# PiezoPreamp_V4-1.net
KiCad netlist of a schematic drawn in EAGLE
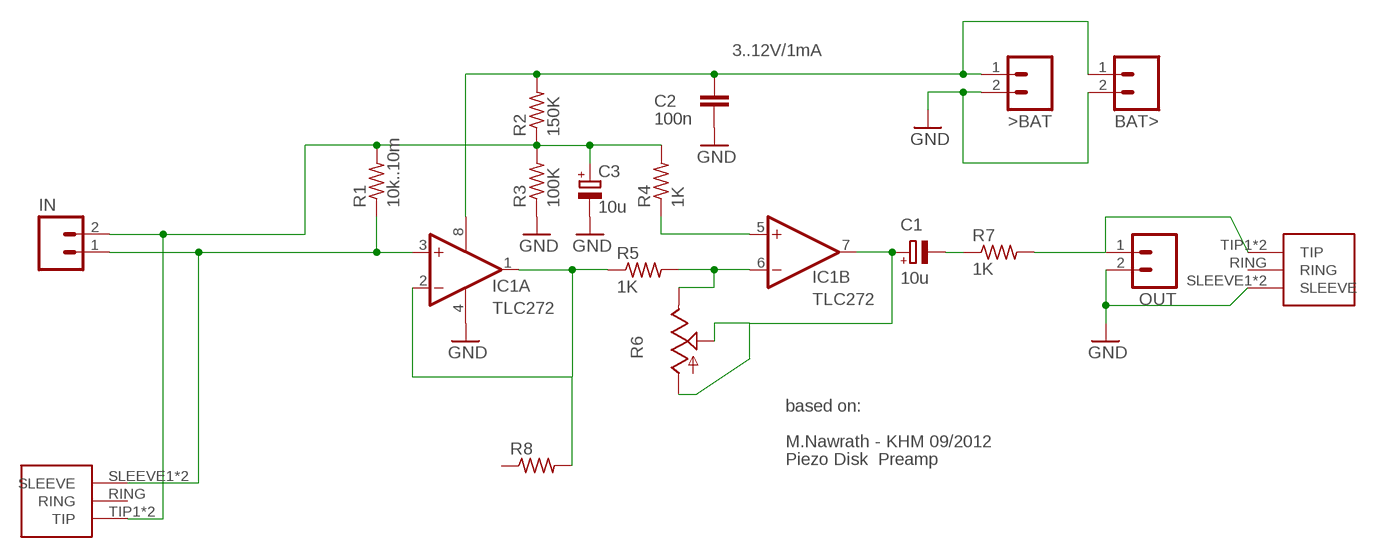
[diagram p0: schematic, sheet 1]

(export (version "E")
  (design (tool "Eeschema 10.0.6"))
  (components
    (comp (ref ">BAT")
      (value "M02LOCK")
      (footprint "eagle-import:1X02_LOCK")
      (libsource (lib "eagle-import") (part "M02LOCK"))
    )
    (comp (ref "BAT>")
      (value "M02LOCK")
      (footprint "eagle-import:1X02_LOCK")
      (libsource (lib "eagle-import") (part "M02LOCK"))
    )
    (comp (ref "C1")
      (value "10u")
      (footprint "eagle-import:E2,5-5")
      (libsource (lib "eagle-import") (part "CPOL-EUE2.5-5"))
    )
    (comp (ref "C2")
      (value "100n")
      (footprint "eagle-import:C025-025X050")
      (libsource (lib "eagle-import") (part "C-EU025-025X050"))
    )
    (comp (ref "C3")
      (value "10u")
      (footprint "eagle-import:E2,5-5")
      (libsource (lib "eagle-import") (part "CPOL-EUE2.5-5"))
    )
    (comp (ref "IC1")
      (value "TLC272")
      (footprint "eagle-import:DIL08")
      (libsource (lib "eagle-import") (part "TLC272P"))
    )
    (comp (ref "IN")
      (value "M02LOCK")
      (footprint "eagle-import:1X02_LOCK")
      (libsource (lib "eagle-import") (part "M02LOCK"))
    )
    (comp (ref "OUT")
      (value "M02LOCK")
      (footprint "eagle-import:1X02_LOCK")
      (libsource (lib "eagle-import") (part "M02LOCK"))
    )
    (comp (ref "OUT1-TRS")
      (value "1/8\"-F-STEREO-PCB")
      (footprint "eagle-import:1_8_-F-STEREO-PCB")
      (libsource (lib "eagle-import") (part "1/8{dblquote}-F-STEREO-PCB"))
    )
    (comp (ref "R1")
      (value "10k..10m")
      (footprint "eagle-import:0204V")
      (libsource (lib "eagle-import") (part "R-US_0204/2V"))
    )
    (comp (ref "R2")
      (value "150K")
      (footprint "eagle-import:0204V")
      (libsource (lib "eagle-import") (part "R-US_0204/2V"))
    )
    (comp (ref "R3")
      (value "100K")
      (footprint "eagle-import:0204V")
      (libsource (lib "eagle-import") (part "R-US_0204/2V"))
    )
    (comp (ref "R4")
      (value "1K")
      (footprint "eagle-import:0204V")
      (libsource (lib "eagle-import") (part "R-US_0204/2V"))
    )
    (comp (ref "R5")
      (value "1K")
      (footprint "eagle-import:0204V")
      (libsource (lib "eagle-import") (part "R-US_0204/2V"))
    )
    (comp (ref "R6")
      (value "TRIM_US-CA6V")
      (footprint "eagle-import:CA6V")
      (libsource (lib "eagle-import") (part "TRIM_US-CA6V"))
    )
    (comp (ref "R7")
      (value "1K")
      (footprint "eagle-import:0204V")
      (libsource (lib "eagle-import") (part "R-US_0204/2V"))
    )
    (comp (ref "R8")
      (value "R-US_0613/5V")
      (footprint "eagle-import:P0613V")
      (libsource (lib "eagle-import") (part "R-US_0613/5V"))
    )
    (comp (ref "U$2")
      (value "1/8\"-F-STEREO-PCB")
      (footprint "eagle-import:1_8_-F-STEREO-PCB")
      (libsource (lib "eagle-import") (part "1/8{dblquote}-F-STEREO-PCB"))
    )
  )
  (nets
    (net (code "1") (name "GND") (class "Default")
      (node (ref ">BAT") (pin "2") (pinfunction "2_2") (pintype "passive"))
      (node (ref "BAT>") (pin "2") (pinfunction "2_2") (pintype "passive"))
      (node (ref "C2") (pin "1") (pinfunction "1_1") (pintype "passive"))
      (node (ref "C3") (pin "-") (pinfunction "-_-") (pintype "passive"))
      (node (ref "IC1") (pin "4") (pinfunction "V-_4") (pintype "power_in"))
      (node (ref "OUT") (pin "2") (pinfunction "2_2") (pintype "passive"))
      (node (ref "OUT1-TRS") (pin "SLEEVE1") (pinfunction "SLEEVE_SLEEVE1") (pintype "bidirectional"))
      (node (ref "OUT1-TRS") (pin "SLEEVE2") (pinfunction "SLEEVE_SLEEVE2") (pintype "bidirectional"))
      (node (ref "R3") (pin "1") (pinfunction "1_1") (pintype "passive"))
    )
    (net (code "2") (name "Net-(C1-Pad-)") (class "Default")
      (node (ref "C1") (pin "-") (pinfunction "-_-") (pintype "passive"))
      (node (ref "R7") (pin "1") (pinfunction "1_1") (pintype "passive"))
    )
    (net (code "3") (name "Net-(C3-Pad+)") (class "Default")
      (node (ref "C3") (pin "+") (pinfunction "+_+") (pintype "passive"))
      (node (ref "IN") (pin "2") (pinfunction "2_2") (pintype "passive"))
      (node (ref "R1") (pin "2") (pinfunction "2_2") (pintype "passive"))
      (node (ref "R2") (pin "1") (pinfunction "1_1") (pintype "passive"))
      (node (ref "R3") (pin "2") (pinfunction "2_2") (pintype "passive"))
      (node (ref "R4") (pin "2") (pinfunction "2_2") (pintype "passive"))
      (node (ref "U$2") (pin "TIP1") (pinfunction "TIP_TIP1") (pintype "bidirectional"))
      (node (ref "U$2") (pin "TIP2") (pinfunction "TIP_TIP2") (pintype "bidirectional"))
    )
    (net (code "4") (name "Net-(IC1A-+IN)") (class "Default")
      (node (ref "IC1") (pin "3") (pinfunction "+IN_3") (pintype "input"))
      (node (ref "IN") (pin "1") (pinfunction "1_1") (pintype "passive"))
      (node (ref "R1") (pin "1") (pinfunction "1_1") (pintype "passive"))
      (node (ref "U$2") (pin "SLEEVE1") (pinfunction "SLEEVE_SLEEVE1") (pintype "bidirectional"))
      (node (ref "U$2") (pin "SLEEVE2") (pinfunction "SLEEVE_SLEEVE2") (pintype "bidirectional"))
    )
    (net (code "5") (name "Net-(IC1A--IN)") (class "Default")
      (node (ref "IC1") (pin "1") (pinfunction "OUT_1") (pintype "output"))
      (node (ref "IC1") (pin "2") (pinfunction "-IN_2") (pintype "input"))
      (node (ref "R5") (pin "1") (pinfunction "1_1") (pintype "passive"))
      (node (ref "R8") (pin "2") (pinfunction "2_2") (pintype "passive"))
    )
    (net (code "6") (name "Net-(IC1B-+IN)") (class "Default")
      (node (ref "IC1") (pin "5") (pinfunction "+IN_5") (pintype "input"))
      (node (ref "R4") (pin "1") (pinfunction "1_1") (pintype "passive"))
    )
    (net (code "7") (name "Net-(IC1B--IN)") (class "Default")
      (node (ref "IC1") (pin "6") (pinfunction "-IN_6") (pintype "input"))
      (node (ref "R5") (pin "2") (pinfunction "2_2") (pintype "passive"))
      (node (ref "R6") (pin "E") (pinfunction "E_E") (pintype "passive"))
    )
    (net (code "8") (name "Net-(IC1B-OUT)") (class "Default")
      (node (ref "C1") (pin "+") (pinfunction "+_+") (pintype "passive"))
      (node (ref "IC1") (pin "7") (pinfunction "OUT_7") (pintype "output"))
      (node (ref "R6") (pin "A") (pinfunction "A_A") (pintype "passive"))
      (node (ref "R6") (pin "S") (pinfunction "S_S") (pintype "passive"))
    )
    (net (code "9") (name "Net-(IC1C-V+)") (class "Default")
      (node (ref ">BAT") (pin "1") (pinfunction "1_1") (pintype "passive"))
      (node (ref "BAT>") (pin "1") (pinfunction "1_1") (pintype "passive"))
      (node (ref "C2") (pin "2") (pinfunction "2_2") (pintype "passive"))
      (node (ref "IC1") (pin "8") (pinfunction "V+_8") (pintype "power_in"))
      (node (ref "R2") (pin "2") (pinfunction "2_2") (pintype "passive"))
    )
    (net (code "10") (name "Net-(OUT-Pad1)") (class "Default")
      (node (ref "OUT") (pin "1") (pinfunction "1_1") (pintype "passive"))
      (node (ref "OUT1-TRS") (pin "TIP1") (pinfunction "TIP_TIP1") (pintype "bidirectional"))
      (node (ref "OUT1-TRS") (pin "TIP2") (pinfunction "TIP_TIP2") (pintype "bidirectional"))
      (node (ref "R7") (pin "2") (pinfunction "2_2") (pintype "passive"))
    )
    (net (code "11") (name "unconnected-(OUT1-TRS-PadRING)") (class "Default")
      (node (ref "OUT1-TRS") (pin "RING") (pinfunction "RING_RING") (pintype "bidirectional"))
    )
    (net (code "12") (name "unconnected-(R8-Pad1)") (class "Default")
      (node (ref "R8") (pin "1") (pinfunction "1_1") (pintype "passive"))
    )
    (net (code "13") (name "unconnected-(U$2-PadRING)") (class "Default")
      (node (ref "U$2") (pin "RING") (pinfunction "RING_RING") (pintype "bidirectional"))
    )
  )
)
